# Controller.net
KiCad netlist of a schematic drawn in Altium Designer
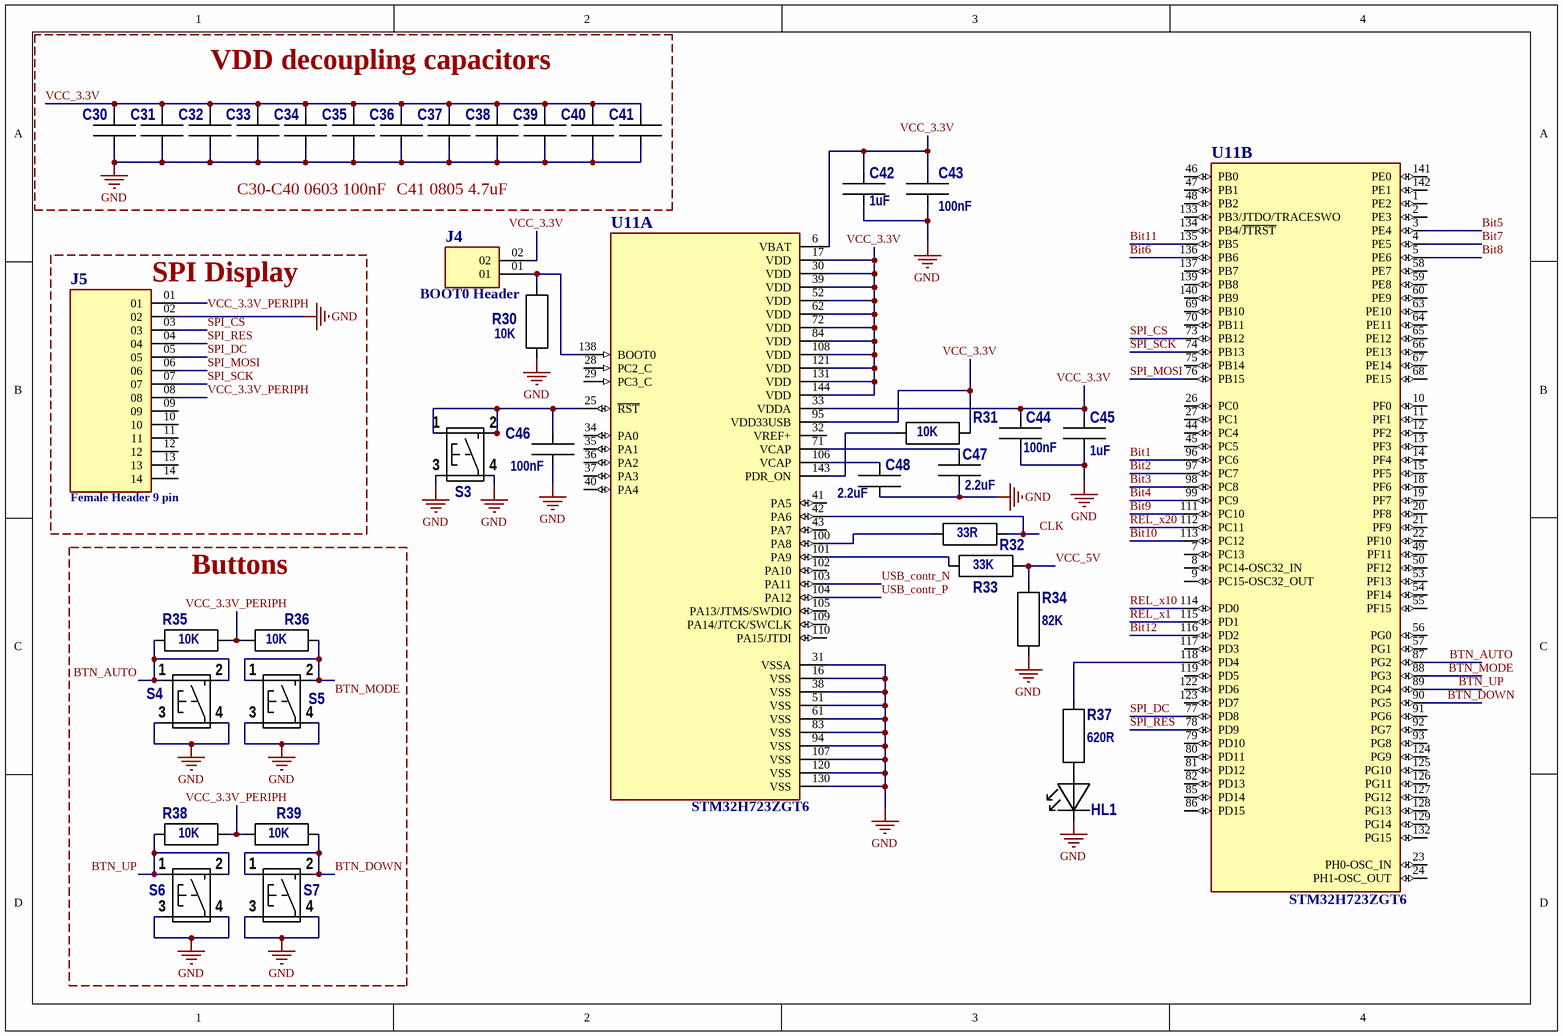
[diagram p0: Controller.SchDoc]

(export (version "E")
  (design (tool "Eeschema 10.0.6"))
  (components
    (comp (ref "C30")
      (value "100nF")
      (footprint "CAP 0603 3D")
      (description "0805 100nF X7R")
      (libsource (lib "RLC V7.1_BVI") (part "C"))
    )
    (comp (ref "C31")
      (value "100nF")
      (footprint "CAP 0603 3D")
      (description "0805 100nF X7R")
      (libsource (lib "RLC V7.1_BVI") (part "C"))
    )
    (comp (ref "C32")
      (value "100nF")
      (footprint "CAP 0603 3D")
      (description "0805 100nF X7R")
      (libsource (lib "RLC V7.1_BVI") (part "C"))
    )
    (comp (ref "C33")
      (value "100nF")
      (footprint "CAP 0603 3D")
      (description "0805 100nF X7R")
      (libsource (lib "RLC V7.1_BVI") (part "C"))
    )
    (comp (ref "C34")
      (value "100nF")
      (footprint "CAP 0603 3D")
      (description "0805 100nF X7R")
      (libsource (lib "RLC V7.1_BVI") (part "C"))
    )
    (comp (ref "C35")
      (value "100nF")
      (footprint "CAP 0603 3D")
      (description "0805 100nF X7R")
      (libsource (lib "RLC V7.1_BVI") (part "C"))
    )
    (comp (ref "C36")
      (value "100nF")
      (footprint "CAP 0603 3D")
      (description "0805 100nF X7R")
      (libsource (lib "RLC V7.1_BVI") (part "C"))
    )
    (comp (ref "C37")
      (value "100nF")
      (footprint "CAP 0603 3D")
      (description "0805 100nF X7R")
      (libsource (lib "RLC V7.1_BVI") (part "C"))
    )
    (comp (ref "C38")
      (value "100nF")
      (footprint "CAP 0603 3D")
      (description "0805 100nF X7R")
      (libsource (lib "RLC V7.1_BVI") (part "C"))
    )
    (comp (ref "C39")
      (value "100nF")
      (footprint "CAP 0603 3D")
      (description "0805 100nF X7R")
      (libsource (lib "RLC V7.1_BVI") (part "C"))
    )
    (comp (ref "C40")
      (value "100nF")
      (footprint "CAP 0603 3D")
      (description "0805 100nF X7R")
      (libsource (lib "RLC V7.1_BVI") (part "C"))
    )
    (comp (ref "C41")
      (value "4.7uF")
      (footprint "Cap 0805 3D")
      (description "0805 4.7 uF min 6V")
      (libsource (lib "RLC V7.1_BVI") (part "C"))
    )
    (comp (ref "C42")
      (value "1uF")
      (footprint "Cap 0805 3D")
      (description "0805 1uF min 6V")
      (libsource (lib "RLC V7.1_BVI") (part "C"))
    )
    (comp (ref "C43")
      (value "100nF")
      (footprint "CAP 0603 3D")
      (description "0603 100nF X7R")
      (libsource (lib "RLC V7.1_BVI") (part "C"))
    )
    (comp (ref "C44")
      (value "100nF")
      (footprint "CAP 0603 3D")
      (description "0603 100nF X7R")
      (libsource (lib "RLC V7.1_BVI") (part "C"))
    )
    (comp (ref "C45")
      (value "1uF")
      (footprint "Cap 0805 3D")
      (description "0805 1 uF X7R")
      (libsource (lib "RLC V7.1_BVI") (part "C"))
    )
    (comp (ref "C46")
      (value "100nF")
      (footprint "CAP 0603 3D")
      (description "0603 100nF X7R")
      (libsource (lib "RLC V7.1_BVI") (part "C"))
    )
    (comp (ref "C47")
      (value "2.2uF")
      (footprint "Cap 0805 3D")
      (description "0805 2.2 uF X7R ESR<100 mOhm")
      (libsource (lib "RLC V7.1_BVI") (part "C"))
    )
    (comp (ref "C48")
      (value "2.2uF")
      (footprint "Cap 0805 3D")
      (description "0805 2.2 uF X7R ESR<100 mOhm")
      (libsource (lib "RLC V7.1_BVI") (part "C"))
    )
    (comp (ref "HL1")
      (value "fyls-0805???")
      (footprint "СД_SMD 2012_110")
      (description "Св. д. ЧИП 2012 (0805)")
      (libsource (lib "HL Светодиоды_V2.6 BVI") (part "fyls-0805...."))
    )
    (comp (ref "J4")
      (value "BOOT0 Header")
      (footprint "SAMTEC_HTSW-102-07-TM-S")
      (fields (field (name "MP") "HTSW10207TMS") (field (name "MF") "Samtec"))
      (libsource (lib "KLS1-2") (part "HTSW-102-07-TM-S"))
    )
    (comp (ref "J5")
      (value "Female Header 9 pin")
      (footprint "SAMTEC_SSQ-114-02-T-S")
      (fields (field (name "MF") "Samtec") (field (name "MP") "SSQ11402TS"))
      (libsource (lib "SSQ-114-02-T-S") (part "SSQ-114-02-T-S"))
    )
    (comp (ref "R30")
      (value "10K")
      (footprint "Res_0603 3D")
      (description "0603 1%")
      (libsource (lib "RLC V7.1_BVI") (part "R"))
    )
    (comp (ref "R31")
      (value "10K")
      (footprint "Res_0603 3D")
      (description "0603 1% 620R")
      (libsource (lib "RLC V7.1_BVI") (part "R"))
    )
    (comp (ref "R32")
      (value "33R")
      (footprint "Res_0603 3D")
      (description "0603 0.1%")
      (libsource (lib "RLC V7.1_BVI") (part "R"))
    )
    (comp (ref "R33")
      (value "33K")
      (footprint "Res_0603 3D")
      (description "0603 1%")
      (libsource (lib "RLC V7.1_BVI") (part "R"))
    )
    (comp (ref "R34")
      (value "82K")
      (footprint "Res_0603 3D")
      (description "0603 1%")
      (libsource (lib "RLC V7.1_BVI") (part "R"))
    )
    (comp (ref "R35")
      (value "10K")
      (footprint "Res_0603 3D")
      (description "0603 1%")
      (libsource (lib "RLC V7.1_BVI") (part "R"))
    )
    (comp (ref "R36")
      (value "10K")
      (footprint "Res_0603 3D")
      (description "0603 1%")
      (libsource (lib "RLC V7.1_BVI") (part "R"))
    )
    (comp (ref "R37")
      (value "620R")
      (footprint "Res_0603 3D")
      (description "0603 1% 620R")
      (libsource (lib "RLC V7.1_BVI") (part "R"))
    )
    (comp (ref "R38")
      (value "10K")
      (footprint "Res_0603 3D")
      (description "0603 1%")
      (libsource (lib "RLC V7.1_BVI") (part "R"))
    )
    (comp (ref "R39")
      (value "10K")
      (footprint "Res_0603 3D")
      (description "0603 1%")
      (libsource (lib "RLC V7.1_BVI") (part "R"))
    )
    (comp (ref "S3")
      (value "SWT-20-12.5")
      (footprint "250 _ 6,0-6,0-12,5")
      (description "Кнопка тактовая")
      (libsource (lib "Switches V3.4_BVI") (part "1_SWT-20-12.5"))
    )
    (comp (ref "S4")
      (value "SWT-20-12.5")
      (footprint "250 _ 6,0-6,0-12,5")
      (description "Кнопка тактовая")
      (libsource (lib "Switches V3.4_BVI") (part "1_SWT-20-12.5"))
    )
    (comp (ref "S5")
      (value "SWT-20-12.5")
      (footprint "250 _ 6,0-6,0-12,5")
      (description "Кнопка тактовая")
      (libsource (lib "Switches V3.4_BVI") (part "1_SWT-20-12.5"))
    )
    (comp (ref "S6")
      (value "SWT-20-12.5")
      (footprint "250 _ 6,0-6,0-12,5")
      (description "Кнопка тактовая")
      (libsource (lib "Switches V3.4_BVI") (part "1_SWT-20-12.5"))
    )
    (comp (ref "S7")
      (value "SWT-20-12.5")
      (footprint "250 _ 6,0-6,0-12,5")
      (description "Кнопка тактовая")
      (libsource (lib "Switches V3.4_BVI") (part "1_SWT-20-12.5"))
    )
    (comp (ref "U11")
      (value "STM32H723ZGT6")
      (footprint "QFP50P2200X2200X160-144N")
      (fields (field (name "MF") "STMicroelectronics"))
      (libsource (lib "STM32H723ZGT6") (part "STM32H723ZGT6"))
    )
  )
  (nets
    (net (code "1") (name "/BTN_AUTO") (class "Default")
      (node (ref "R35") (pin "2") (pintype "passive"))
      (node (ref "S4") (pin "1") (pinfunction "1_1") (pintype "passive"))
      (node (ref "S4") (pin "2") (pinfunction "2_2") (pintype "passive"))
      (node (ref "U11") (pin "87") (pinfunction "PG2_87") (pintype "bidirectional"))
    )
    (net (code "2") (name "/BTN_DOWN") (class "Default")
      (node (ref "R39") (pin "1") (pintype "passive"))
      (node (ref "S7") (pin "1") (pinfunction "1_1") (pintype "passive"))
      (node (ref "S7") (pin "2") (pinfunction "2_2") (pintype "passive"))
      (node (ref "U11") (pin "90") (pinfunction "PG5_90") (pintype "bidirectional"))
    )
    (net (code "3") (name "/BTN_MODE") (class "Default")
      (node (ref "R36") (pin "1") (pintype "passive"))
      (node (ref "S5") (pin "1") (pinfunction "1_1") (pintype "passive"))
      (node (ref "S5") (pin "2") (pinfunction "2_2") (pintype "passive"))
      (node (ref "U11") (pin "88") (pinfunction "PG3_88") (pintype "bidirectional"))
    )
    (net (code "4") (name "/BTN_UP") (class "Default")
      (node (ref "R38") (pin "2") (pintype "passive"))
      (node (ref "S6") (pin "1") (pinfunction "1_1") (pintype "passive"))
      (node (ref "S6") (pin "2") (pinfunction "2_2") (pintype "passive"))
      (node (ref "U11") (pin "89") (pinfunction "PG4_89") (pintype "bidirectional"))
    )
    (net (code "5") (name "/Bit1") (class "Default")
      (node (ref "U11") (pin "96") (pinfunction "PC6_96") (pintype "bidirectional"))
    )
    (net (code "6") (name "/Bit2") (class "Default")
      (node (ref "U11") (pin "97") (pinfunction "PC7_97") (pintype "bidirectional"))
    )
    (net (code "7") (name "/Bit3") (class "Default")
      (node (ref "U11") (pin "98") (pinfunction "PC8_98") (pintype "bidirectional"))
    )
    (net (code "8") (name "/Bit4") (class "Default")
      (node (ref "U11") (pin "99") (pinfunction "PC9_99") (pintype "bidirectional"))
    )
    (net (code "9") (name "/Bit5") (class "Default")
      (node (ref "U11") (pin "3") (pinfunction "PE4_3") (pintype "bidirectional"))
    )
    (net (code "10") (name "/Bit6") (class "Default")
      (node (ref "U11") (pin "136") (pinfunction "PB6_136") (pintype "bidirectional"))
    )
    (net (code "11") (name "/Bit7") (class "Default")
      (node (ref "U11") (pin "4") (pinfunction "PE5_4") (pintype "bidirectional"))
    )
    (net (code "12") (name "/Bit8") (class "Default")
      (node (ref "U11") (pin "5") (pinfunction "PE6_5") (pintype "bidirectional"))
    )
    (net (code "13") (name "/Bit9") (class "Default")
      (node (ref "U11") (pin "111") (pinfunction "PC10_111") (pintype "bidirectional"))
    )
    (net (code "14") (name "/Bit10") (class "Default")
      (node (ref "U11") (pin "113") (pinfunction "PC12_113") (pintype "bidirectional"))
    )
    (net (code "15") (name "/Bit11") (class "Default")
      (node (ref "U11") (pin "135") (pinfunction "PB5_135") (pintype "bidirectional"))
    )
    (net (code "16") (name "/Bit12") (class "Default")
      (node (ref "U11") (pin "116") (pinfunction "PD2_116") (pintype "bidirectional"))
    )
    (net (code "17") (name "/CLK") (class "Default")
      (node (ref "R32") (pin "1") (pintype "passive"))
      (node (ref "U11") (pin "42") (pinfunction "PA6_42") (pintype "bidirectional"))
    )
    (net (code "18") (name "/REL_x1") (class "Default")
      (node (ref "U11") (pin "115") (pinfunction "PD1_115") (pintype "bidirectional"))
    )
    (net (code "19") (name "/REL_x10") (class "Default")
      (node (ref "U11") (pin "114") (pinfunction "PD0_114") (pintype "bidirectional"))
    )
    (net (code "20") (name "/REL_x20") (class "Default")
      (node (ref "U11") (pin "112") (pinfunction "PC11_112") (pintype "bidirectional"))
    )
    (net (code "21") (name "/SPI_CS") (class "Default")
      (node (ref "J5") (pin "03") (pinfunction "03_03") (pintype "passive"))
      (node (ref "U11") (pin "73") (pinfunction "PB12_73") (pintype "bidirectional"))
    )
    (net (code "22") (name "/SPI_DC") (class "Default")
      (node (ref "J5") (pin "05") (pinfunction "05_05") (pintype "passive"))
      (node (ref "U11") (pin "77") (pinfunction "PD8_77") (pintype "bidirectional"))
    )
    (net (code "23") (name "/SPI_MOSI") (class "Default")
      (node (ref "J5") (pin "06") (pinfunction "06_06") (pintype "passive"))
      (node (ref "U11") (pin "76") (pinfunction "PB15_76") (pintype "bidirectional"))
    )
    (net (code "24") (name "/SPI_RES") (class "Default")
      (node (ref "J5") (pin "04") (pinfunction "04_04") (pintype "passive"))
      (node (ref "U11") (pin "78") (pinfunction "PD9_78") (pintype "bidirectional"))
    )
    (net (code "25") (name "/SPI_SCK") (class "Default")
      (node (ref "J5") (pin "07") (pinfunction "07_07") (pintype "passive"))
      (node (ref "U11") (pin "74") (pinfunction "PB13_74") (pintype "bidirectional"))
    )
    (net (code "26") (name "/USB_contr_N") (class "Default")
      (node (ref "U11") (pin "103") (pinfunction "PA11_103") (pintype "bidirectional"))
    )
    (net (code "27") (name "/USB_contr_P") (class "Default")
      (node (ref "U11") (pin "104") (pinfunction "PA12_104") (pintype "bidirectional"))
    )
    (net (code "28") (name "/VCC_3.3V") (class "Default")
      (node (ref "C30") (pin "2") (pintype "passive"))
      (node (ref "C31") (pin "2") (pintype "passive"))
      (node (ref "C32") (pin "2") (pintype "passive"))
      (node (ref "C33") (pin "2") (pintype "passive"))
      (node (ref "C34") (pin "2") (pintype "passive"))
      (node (ref "C35") (pin "2") (pintype "passive"))
      (node (ref "C36") (pin "2") (pintype "passive"))
      (node (ref "C37") (pin "2") (pintype "passive"))
      (node (ref "C38") (pin "2") (pintype "passive"))
      (node (ref "C39") (pin "2") (pintype "passive"))
      (node (ref "C40") (pin "1") (pintype "passive"))
      (node (ref "C41") (pin "2") (pintype "passive"))
      (node (ref "C42") (pin "2") (pintype "passive"))
      (node (ref "C43") (pin "1") (pintype "passive"))
      (node (ref "C44") (pin "1") (pintype "passive"))
      (node (ref "C45") (pin "2") (pintype "passive"))
      (node (ref "J4") (pin "02") (pinfunction "02_02") (pintype "passive"))
      (node (ref "R31") (pin "1") (pintype "passive"))
      (node (ref "U11") (pin "108") (pinfunction "VDD_108") (pintype "power_in"))
      (node (ref "U11") (pin "121") (pinfunction "VDD_121") (pintype "power_in"))
      (node (ref "U11") (pin "131") (pinfunction "VDD_131") (pintype "power_in"))
      (node (ref "U11") (pin "144") (pinfunction "VDD_144") (pintype "power_in"))
      (node (ref "U11") (pin "17") (pinfunction "VDD_17") (pintype "power_in"))
      (node (ref "U11") (pin "30") (pinfunction "VDD_30") (pintype "power_in"))
      (node (ref "U11") (pin "33") (pinfunction "VDDA_33") (pintype "power_in"))
      (node (ref "U11") (pin "39") (pinfunction "VDD_39") (pintype "power_in"))
      (node (ref "U11") (pin "52") (pinfunction "VDD_52") (pintype "power_in"))
      (node (ref "U11") (pin "6") (pinfunction "VBAT_6") (pintype "power_in"))
      (node (ref "U11") (pin "62") (pinfunction "VDD_62") (pintype "power_in"))
      (node (ref "U11") (pin "72") (pinfunction "VDD_72") (pintype "power_in"))
      (node (ref "U11") (pin "84") (pinfunction "VDD_84") (pintype "power_in"))
      (node (ref "U11") (pin "95") (pinfunction "VDD33USB_95") (pintype "power_in"))
    )
    (net (code "29") (name "/VCC_3.3V_PERIPH") (class "Default")
      (node (ref "J5") (pin "01") (pinfunction "01_01") (pintype "passive"))
      (node (ref "J5") (pin "08") (pinfunction "08_08") (pintype "passive"))
      (node (ref "R35") (pin "1") (pintype "passive"))
      (node (ref "R36") (pin "2") (pintype "passive"))
      (node (ref "R38") (pin "1") (pintype "passive"))
      (node (ref "R39") (pin "2") (pintype "passive"))
    )
    (net (code "30") (name "/VCC_5V") (class "Default")
      (node (ref "R33") (pin "1") (pintype "passive"))
      (node (ref "R34") (pin "1") (pintype "passive"))
    )
    (net (code "31") (name "GND") (class "Default")
      (node (ref "C30") (pin "1") (pintype "passive"))
      (node (ref "C31") (pin "1") (pintype "passive"))
      (node (ref "C32") (pin "1") (pintype "passive"))
      (node (ref "C33") (pin "1") (pintype "passive"))
      (node (ref "C34") (pin "1") (pintype "passive"))
      (node (ref "C35") (pin "1") (pintype "passive"))
      (node (ref "C36") (pin "1") (pintype "passive"))
      (node (ref "C37") (pin "1") (pintype "passive"))
      (node (ref "C38") (pin "1") (pintype "passive"))
      (node (ref "C39") (pin "1") (pintype "passive"))
      (node (ref "C40") (pin "2") (pintype "passive"))
      (node (ref "C41") (pin "1") (pintype "passive"))
      (node (ref "C42") (pin "1") (pintype "passive"))
      (node (ref "C43") (pin "2") (pintype "passive"))
      (node (ref "C44") (pin "2") (pintype "passive"))
      (node (ref "C45") (pin "1") (pintype "passive"))
      (node (ref "C46") (pin "2") (pintype "passive"))
      (node (ref "C47") (pin "1") (pintype "passive"))
      (node (ref "C48") (pin "1") (pintype "passive"))
      (node (ref "HL1") (pin "1") (pinfunction "K_1") (pintype "passive"))
      (node (ref "J5") (pin "02") (pinfunction "02_02") (pintype "passive"))
      (node (ref "R30") (pin "1") (pintype "passive"))
      (node (ref "R34") (pin "2") (pintype "passive"))
      (node (ref "S3") (pin "3") (pinfunction "3_3") (pintype "passive"))
      (node (ref "S3") (pin "4") (pinfunction "4_4") (pintype "passive"))
      (node (ref "S4") (pin "3") (pinfunction "3_3") (pintype "passive"))
      (node (ref "S4") (pin "4") (pinfunction "4_4") (pintype "passive"))
      (node (ref "S5") (pin "3") (pinfunction "3_3") (pintype "passive"))
      (node (ref "S5") (pin "4") (pinfunction "4_4") (pintype "passive"))
      (node (ref "S6") (pin "3") (pinfunction "3_3") (pintype "passive"))
      (node (ref "S6") (pin "4") (pinfunction "4_4") (pintype "passive"))
      (node (ref "S7") (pin "3") (pinfunction "3_3") (pintype "passive"))
      (node (ref "S7") (pin "4") (pinfunction "4_4") (pintype "passive"))
      (node (ref "U11") (pin "107") (pinfunction "VSS_107") (pintype "power_in"))
      (node (ref "U11") (pin "120") (pinfunction "VSS_120") (pintype "power_in"))
      (node (ref "U11") (pin "130") (pinfunction "VSS_130") (pintype "power_in"))
      (node (ref "U11") (pin "16") (pinfunction "VSS_16") (pintype "power_in"))
      (node (ref "U11") (pin "31") (pinfunction "VSSA_31") (pintype "power_in"))
      (node (ref "U11") (pin "38") (pinfunction "VSS_38") (pintype "power_in"))
      (node (ref "U11") (pin "51") (pinfunction "VSS_51") (pintype "power_in"))
      (node (ref "U11") (pin "61") (pinfunction "VSS_61") (pintype "power_in"))
      (node (ref "U11") (pin "83") (pinfunction "VSS_83") (pintype "power_in"))
      (node (ref "U11") (pin "94") (pinfunction "VSS_94") (pintype "power_in"))
    )
    (net (code "32") (name "Net-(C47-Pad2)") (class "Default")
      (node (ref "C47") (pin "2") (pintype "passive"))
      (node (ref "U11") (pin "71") (pinfunction "VCAP_71") (pintype "power_in"))
    )
    (net (code "33") (name "Net-(C48-Pad2)") (class "Default")
      (node (ref "C48") (pin "2") (pintype "passive"))
      (node (ref "U11") (pin "106") (pinfunction "VCAP_106") (pintype "power_in"))
    )
    (net (code "34") (name "Net-(HL1-A)") (class "Default")
      (node (ref "HL1") (pin "2") (pinfunction "A_2") (pintype "passive"))
      (node (ref "R37") (pin "2") (pintype "passive"))
    )
    (net (code "35") (name "Net-(U11A-BOOT0)") (class "Default")
      (node (ref "J4") (pin "01") (pinfunction "01_01") (pintype "passive"))
      (node (ref "R30") (pin "2") (pintype "passive"))
      (node (ref "U11") (pin "138") (pinfunction "BOOT0_138") (pintype "input"))
    )
    (net (code "36") (name "Net-(U11A-PA8)") (class "Default")
      (node (ref "R32") (pin "2") (pintype "passive"))
      (node (ref "U11") (pin "100") (pinfunction "PA8_100") (pintype "bidirectional"))
    )
    (net (code "37") (name "Net-(U11A-PA9)") (class "Default")
      (node (ref "R33") (pin "2") (pintype "passive"))
      (node (ref "U11") (pin "101") (pinfunction "PA9_101") (pintype "bidirectional"))
    )
    (net (code "38") (name "Net-(U11A-PDR_ON)") (class "Default")
      (node (ref "R31") (pin "2") (pintype "passive"))
      (node (ref "U11") (pin "143") (pinfunction "PDR_ON_143") (pintype "power_in"))
    )
    (net (code "39") (name "Net-(U11A-~{RST})") (class "Default")
      (node (ref "C46") (pin "1") (pintype "passive"))
      (node (ref "S3") (pin "1") (pinfunction "1_1") (pintype "passive"))
      (node (ref "S3") (pin "2") (pinfunction "2_2") (pintype "passive"))
      (node (ref "U11") (pin "25") (pinfunction "~{RST}_25") (pintype "bidirectional"))
    )
    (net (code "40") (name "Net-(U11B-PD4)") (class "Default")
      (node (ref "R37") (pin "1") (pintype "passive"))
      (node (ref "U11") (pin "118") (pinfunction "PD4_118") (pintype "bidirectional"))
    )
    (net (code "41") (name "unconnected-(J5-Pad09)") (class "Default")
      (node (ref "J5") (pin "09") (pinfunction "09_09") (pintype "passive"))
    )
    (net (code "42") (name "unconnected-(J5-Pad10)") (class "Default")
      (node (ref "J5") (pin "10") (pinfunction "10_10") (pintype "passive"))
    )
    (net (code "43") (name "unconnected-(J5-Pad11)") (class "Default")
      (node (ref "J5") (pin "11") (pinfunction "11_11") (pintype "passive"))
    )
    (net (code "44") (name "unconnected-(J5-Pad12)") (class "Default")
      (node (ref "J5") (pin "12") (pinfunction "12_12") (pintype "passive"))
    )
    (net (code "45") (name "unconnected-(J5-Pad13)") (class "Default")
      (node (ref "J5") (pin "13") (pinfunction "13_13") (pintype "passive"))
    )
    (net (code "46") (name "unconnected-(J5-Pad14)") (class "Default")
      (node (ref "J5") (pin "14") (pinfunction "14_14") (pintype "passive"))
    )
    (net (code "47") (name "unconnected-(U11A-PA0-Pad34)") (class "Default")
      (node (ref "U11") (pin "34") (pinfunction "PA0_34") (pintype "bidirectional"))
    )
    (net (code "48") (name "unconnected-(U11A-PA1-Pad35)") (class "Default")
      (node (ref "U11") (pin "35") (pinfunction "PA1_35") (pintype "bidirectional"))
    )
    (net (code "49") (name "unconnected-(U11A-PA2-Pad36)") (class "Default")
      (node (ref "U11") (pin "36") (pinfunction "PA2_36") (pintype "bidirectional"))
    )
    (net (code "50") (name "unconnected-(U11A-PA3-Pad37)") (class "Default")
      (node (ref "U11") (pin "37") (pinfunction "PA3_37") (pintype "bidirectional"))
    )
    (net (code "51") (name "unconnected-(U11A-PA4-Pad40)") (class "Default")
      (node (ref "U11") (pin "40") (pinfunction "PA4_40") (pintype "bidirectional"))
    )
    (net (code "52") (name "unconnected-(U11A-PA5-Pad41)") (class "Default")
      (node (ref "U11") (pin "41") (pinfunction "PA5_41") (pintype "bidirectional"))
    )
    (net (code "53") (name "unconnected-(U11A-PA7-Pad43)") (class "Default")
      (node (ref "U11") (pin "43") (pinfunction "PA7_43") (pintype "bidirectional"))
    )
    (net (code "54") (name "unconnected-(U11A-PA10-Pad102)") (class "Default")
      (node (ref "U11") (pin "102") (pinfunction "PA10_102") (pintype "bidirectional"))
    )
    (net (code "55") (name "unconnected-(U11A-PA13{slash}JTMS{slash}SWDIO-Pad105)") (class "Default")
      (node (ref "U11") (pin "105") (pinfunction "PA13/JTMS/SWDIO_105") (pintype "bidirectional"))
    )
    (net (code "56") (name "unconnected-(U11A-PA14{slash}JTCK{slash}SWCLK-Pad109)") (class "Default")
      (node (ref "U11") (pin "109") (pinfunction "PA14/JTCK/SWCLK_109") (pintype "bidirectional"))
    )
    (net (code "57") (name "unconnected-(U11A-PA15{slash}JTDI-Pad110)") (class "Default")
      (node (ref "U11") (pin "110") (pinfunction "PA15/JTDI_110") (pintype "bidirectional"))
    )
    (net (code "58") (name "unconnected-(U11A-PC2_C-Pad28)") (class "Default")
      (node (ref "U11") (pin "28") (pinfunction "PC2_C_28") (pintype "input"))
    )
    (net (code "59") (name "unconnected-(U11A-PC3_C-Pad29)") (class "Default")
      (node (ref "U11") (pin "29") (pinfunction "PC3_C_29") (pintype "input"))
    )
    (net (code "60") (name "unconnected-(U11A-VREF+-Pad32)") (class "Default")
      (node (ref "U11") (pin "32") (pinfunction "VREF+_32") (pintype "power_in"))
    )
    (net (code "61") (name "unconnected-(U11B-PB0-Pad46)") (class "Default")
      (node (ref "U11") (pin "46") (pinfunction "PB0_46") (pintype "bidirectional"))
    )
    (net (code "62") (name "unconnected-(U11B-PB1-Pad47)") (class "Default")
      (node (ref "U11") (pin "47") (pinfunction "PB1_47") (pintype "bidirectional"))
    )
    (net (code "63") (name "unconnected-(U11B-PB2-Pad48)") (class "Default")
      (node (ref "U11") (pin "48") (pinfunction "PB2_48") (pintype "bidirectional"))
    )
    (net (code "64") (name "unconnected-(U11B-PB3{slash}JTDO{slash}TRACESWO-Pad133)") (class "Default")
      (node (ref "U11") (pin "133") (pinfunction "PB3/JTDO/TRACESWO_133") (pintype "bidirectional"))
    )
    (net (code "65") (name "unconnected-(U11B-PB4{slash}~{JTRST}-Pad134)") (class "Default")
      (node (ref "U11") (pin "134") (pinfunction "PB4/~{JTRST}_134") (pintype "bidirectional"))
    )
    (net (code "66") (name "unconnected-(U11B-PB7-Pad137)") (class "Default")
      (node (ref "U11") (pin "137") (pinfunction "PB7_137") (pintype "bidirectional"))
    )
    (net (code "67") (name "unconnected-(U11B-PB8-Pad139)") (class "Default")
      (node (ref "U11") (pin "139") (pinfunction "PB8_139") (pintype "bidirectional"))
    )
    (net (code "68") (name "unconnected-(U11B-PB9-Pad140)") (class "Default")
      (node (ref "U11") (pin "140") (pinfunction "PB9_140") (pintype "bidirectional"))
    )
    (net (code "69") (name "unconnected-(U11B-PB10-Pad69)") (class "Default")
      (node (ref "U11") (pin "69") (pinfunction "PB10_69") (pintype "bidirectional"))
    )
    (net (code "70") (name "unconnected-(U11B-PB11-Pad70)") (class "Default")
      (node (ref "U11") (pin "70") (pinfunction "PB11_70") (pintype "bidirectional"))
    )
    (net (code "71") (name "unconnected-(U11B-PB14-Pad75)") (class "Default")
      (node (ref "U11") (pin "75") (pinfunction "PB14_75") (pintype "bidirectional"))
    )
    (net (code "72") (name "unconnected-(U11B-PC0-Pad26)") (class "Default")
      (node (ref "U11") (pin "26") (pinfunction "PC0_26") (pintype "bidirectional"))
    )
    (net (code "73") (name "unconnected-(U11B-PC1-Pad27)") (class "Default")
      (node (ref "U11") (pin "27") (pinfunction "PC1_27") (pintype "bidirectional"))
    )
    (net (code "74") (name "unconnected-(U11B-PC4-Pad44)") (class "Default")
      (node (ref "U11") (pin "44") (pinfunction "PC4_44") (pintype "bidirectional"))
    )
    (net (code "75") (name "unconnected-(U11B-PC5-Pad45)") (class "Default")
      (node (ref "U11") (pin "45") (pinfunction "PC5_45") (pintype "bidirectional"))
    )
    (net (code "76") (name "unconnected-(U11B-PC13-Pad7)") (class "Default")
      (node (ref "U11") (pin "7") (pinfunction "PC13_7") (pintype "bidirectional"))
    )
    (net (code "77") (name "unconnected-(U11B-PC14-OSC32_IN-Pad8)") (class "Default")
      (node (ref "U11") (pin "8") (pinfunction "PC14-OSC32_IN_8") (pintype "bidirectional"))
    )
    (net (code "78") (name "unconnected-(U11B-PC15-OSC32_OUT-Pad9)") (class "Default")
      (node (ref "U11") (pin "9") (pinfunction "PC15-OSC32_OUT_9") (pintype "bidirectional"))
    )
    (net (code "79") (name "unconnected-(U11B-PD3-Pad117)") (class "Default")
      (node (ref "U11") (pin "117") (pinfunction "PD3_117") (pintype "bidirectional"))
    )
    (net (code "80") (name "unconnected-(U11B-PD5-Pad119)") (class "Default")
      (node (ref "U11") (pin "119") (pinfunction "PD5_119") (pintype "bidirectional"))
    )
    (net (code "81") (name "unconnected-(U11B-PD6-Pad122)") (class "Default")
      (node (ref "U11") (pin "122") (pinfunction "PD6_122") (pintype "bidirectional"))
    )
    (net (code "82") (name "unconnected-(U11B-PD7-Pad123)") (class "Default")
      (node (ref "U11") (pin "123") (pinfunction "PD7_123") (pintype "bidirectional"))
    )
    (net (code "83") (name "unconnected-(U11B-PD10-Pad79)") (class "Default")
      (node (ref "U11") (pin "79") (pinfunction "PD10_79") (pintype "bidirectional"))
    )
    (net (code "84") (name "unconnected-(U11B-PD11-Pad80)") (class "Default")
      (node (ref "U11") (pin "80") (pinfunction "PD11_80") (pintype "bidirectional"))
    )
    (net (code "85") (name "unconnected-(U11B-PD12-Pad81)") (class "Default")
      (node (ref "U11") (pin "81") (pinfunction "PD12_81") (pintype "bidirectional"))
    )
    (net (code "86") (name "unconnected-(U11B-PD13-Pad82)") (class "Default")
      (node (ref "U11") (pin "82") (pinfunction "PD13_82") (pintype "bidirectional"))
    )
    (net (code "87") (name "unconnected-(U11B-PD14-Pad85)") (class "Default")
      (node (ref "U11") (pin "85") (pinfunction "PD14_85") (pintype "bidirectional"))
    )
    (net (code "88") (name "unconnected-(U11B-PD15-Pad86)") (class "Default")
      (node (ref "U11") (pin "86") (pinfunction "PD15_86") (pintype "bidirectional"))
    )
    (net (code "89") (name "unconnected-(U11B-PE0-Pad141)") (class "Default")
      (node (ref "U11") (pin "141") (pinfunction "PE0_141") (pintype "bidirectional"))
    )
    (net (code "90") (name "unconnected-(U11B-PE1-Pad142)") (class "Default")
      (node (ref "U11") (pin "142") (pinfunction "PE1_142") (pintype "bidirectional"))
    )
    (net (code "91") (name "unconnected-(U11B-PE2-Pad1)") (class "Default")
      (node (ref "U11") (pin "1") (pinfunction "PE2_1") (pintype "bidirectional"))
    )
    (net (code "92") (name "unconnected-(U11B-PE3-Pad2)") (class "Default")
      (node (ref "U11") (pin "2") (pinfunction "PE3_2") (pintype "bidirectional"))
    )
    (net (code "93") (name "unconnected-(U11B-PE7-Pad58)") (class "Default")
      (node (ref "U11") (pin "58") (pinfunction "PE7_58") (pintype "bidirectional"))
    )
    (net (code "94") (name "unconnected-(U11B-PE8-Pad59)") (class "Default")
      (node (ref "U11") (pin "59") (pinfunction "PE8_59") (pintype "bidirectional"))
    )
    (net (code "95") (name "unconnected-(U11B-PE9-Pad60)") (class "Default")
      (node (ref "U11") (pin "60") (pinfunction "PE9_60") (pintype "bidirectional"))
    )
    (net (code "96") (name "unconnected-(U11B-PE10-Pad63)") (class "Default")
      (node (ref "U11") (pin "63") (pinfunction "PE10_63") (pintype "bidirectional"))
    )
    (net (code "97") (name "unconnected-(U11B-PE11-Pad64)") (class "Default")
      (node (ref "U11") (pin "64") (pinfunction "PE11_64") (pintype "bidirectional"))
    )
    (net (code "98") (name "unconnected-(U11B-PE12-Pad65)") (class "Default")
      (node (ref "U11") (pin "65") (pinfunction "PE12_65") (pintype "bidirectional"))
    )
    (net (code "99") (name "unconnected-(U11B-PE13-Pad66)") (class "Default")
      (node (ref "U11") (pin "66") (pinfunction "PE13_66") (pintype "bidirectional"))
    )
    (net (code "100") (name "unconnected-(U11B-PE14-Pad67)") (class "Default")
      (node (ref "U11") (pin "67") (pinfunction "PE14_67") (pintype "bidirectional"))
    )
    (net (code "101") (name "unconnected-(U11B-PE15-Pad68)") (class "Default")
      (node (ref "U11") (pin "68") (pinfunction "PE15_68") (pintype "bidirectional"))
    )
    (net (code "102") (name "unconnected-(U11B-PF0-Pad10)") (class "Default")
      (node (ref "U11") (pin "10") (pinfunction "PF0_10") (pintype "bidirectional"))
    )
    (net (code "103") (name "unconnected-(U11B-PF1-Pad11)") (class "Default")
      (node (ref "U11") (pin "11") (pinfunction "PF1_11") (pintype "bidirectional"))
    )
    (net (code "104") (name "unconnected-(U11B-PF2-Pad12)") (class "Default")
      (node (ref "U11") (pin "12") (pinfunction "PF2_12") (pintype "bidirectional"))
    )
    (net (code "105") (name "unconnected-(U11B-PF3-Pad13)") (class "Default")
      (node (ref "U11") (pin "13") (pinfunction "PF3_13") (pintype "bidirectional"))
    )
    (net (code "106") (name "unconnected-(U11B-PF4-Pad14)") (class "Default")
      (node (ref "U11") (pin "14") (pinfunction "PF4_14") (pintype "bidirectional"))
    )
    (net (code "107") (name "unconnected-(U11B-PF5-Pad15)") (class "Default")
      (node (ref "U11") (pin "15") (pinfunction "PF5_15") (pintype "bidirectional"))
    )
    (net (code "108") (name "unconnected-(U11B-PF6-Pad18)") (class "Default")
      (node (ref "U11") (pin "18") (pinfunction "PF6_18") (pintype "bidirectional"))
    )
    (net (code "109") (name "unconnected-(U11B-PF7-Pad19)") (class "Default")
      (node (ref "U11") (pin "19") (pinfunction "PF7_19") (pintype "bidirectional"))
    )
    (net (code "110") (name "unconnected-(U11B-PF8-Pad20)") (class "Default")
      (node (ref "U11") (pin "20") (pinfunction "PF8_20") (pintype "bidirectional"))
    )
    (net (code "111") (name "unconnected-(U11B-PF9-Pad21)") (class "Default")
      (node (ref "U11") (pin "21") (pinfunction "PF9_21") (pintype "bidirectional"))
    )
    (net (code "112") (name "unconnected-(U11B-PF10-Pad22)") (class "Default")
      (node (ref "U11") (pin "22") (pinfunction "PF10_22") (pintype "bidirectional"))
    )
    (net (code "113") (name "unconnected-(U11B-PF11-Pad49)") (class "Default")
      (node (ref "U11") (pin "49") (pinfunction "PF11_49") (pintype "bidirectional"))
    )
    (net (code "114") (name "unconnected-(U11B-PF12-Pad50)") (class "Default")
      (node (ref "U11") (pin "50") (pinfunction "PF12_50") (pintype "bidirectional"))
    )
    (net (code "115") (name "unconnected-(U11B-PF13-Pad53)") (class "Default")
      (node (ref "U11") (pin "53") (pinfunction "PF13_53") (pintype "bidirectional"))
    )
    (net (code "116") (name "unconnected-(U11B-PF14-Pad54)") (class "Default")
      (node (ref "U11") (pin "54") (pinfunction "PF14_54") (pintype "bidirectional"))
    )
    (net (code "117") (name "unconnected-(U11B-PF15-Pad55)") (class "Default")
      (node (ref "U11") (pin "55") (pinfunction "PF15_55") (pintype "bidirectional"))
    )
    (net (code "118") (name "unconnected-(U11B-PG0-Pad56)") (class "Default")
      (node (ref "U11") (pin "56") (pinfunction "PG0_56") (pintype "bidirectional"))
    )
    (net (code "119") (name "unconnected-(U11B-PG1-Pad57)") (class "Default")
      (node (ref "U11") (pin "57") (pinfunction "PG1_57") (pintype "bidirectional"))
    )
    (net (code "120") (name "unconnected-(U11B-PG6-Pad91)") (class "Default")
      (node (ref "U11") (pin "91") (pinfunction "PG6_91") (pintype "bidirectional"))
    )
    (net (code "121") (name "unconnected-(U11B-PG7-Pad92)") (class "Default")
      (node (ref "U11") (pin "92") (pinfunction "PG7_92") (pintype "bidirectional"))
    )
    (net (code "122") (name "unconnected-(U11B-PG8-Pad93)") (class "Default")
      (node (ref "U11") (pin "93") (pinfunction "PG8_93") (pintype "bidirectional"))
    )
    (net (code "123") (name "unconnected-(U11B-PG9-Pad124)") (class "Default")
      (node (ref "U11") (pin "124") (pinfunction "PG9_124") (pintype "bidirectional"))
    )
    (net (code "124") (name "unconnected-(U11B-PG10-Pad125)") (class "Default")
      (node (ref "U11") (pin "125") (pinfunction "PG10_125") (pintype "bidirectional"))
    )
    (net (code "125") (name "unconnected-(U11B-PG11-Pad126)") (class "Default")
      (node (ref "U11") (pin "126") (pinfunction "PG11_126") (pintype "bidirectional"))
    )
    (net (code "126") (name "unconnected-(U11B-PG12-Pad127)") (class "Default")
      (node (ref "U11") (pin "127") (pinfunction "PG12_127") (pintype "bidirectional"))
    )
    (net (code "127") (name "unconnected-(U11B-PG13-Pad128)") (class "Default")
      (node (ref "U11") (pin "128") (pinfunction "PG13_128") (pintype "bidirectional"))
    )
    (net (code "128") (name "unconnected-(U11B-PG14-Pad129)") (class "Default")
      (node (ref "U11") (pin "129") (pinfunction "PG14_129") (pintype "bidirectional"))
    )
    (net (code "129") (name "unconnected-(U11B-PG15-Pad132)") (class "Default")
      (node (ref "U11") (pin "132") (pinfunction "PG15_132") (pintype "bidirectional"))
    )
    (net (code "130") (name "unconnected-(U11B-PH0-OSC_IN-Pad23)") (class "Default")
      (node (ref "U11") (pin "23") (pinfunction "PH0-OSC_IN_23") (pintype "bidirectional"))
    )
    (net (code "131") (name "unconnected-(U11B-PH1-OSC_OUT-Pad24)") (class "Default")
      (node (ref "U11") (pin "24") (pinfunction "PH1-OSC_OUT_24") (pintype "bidirectional"))
    )
  )
)
